# hw-proto01.net
KiCad netlist of a schematic drawn in EAGLE
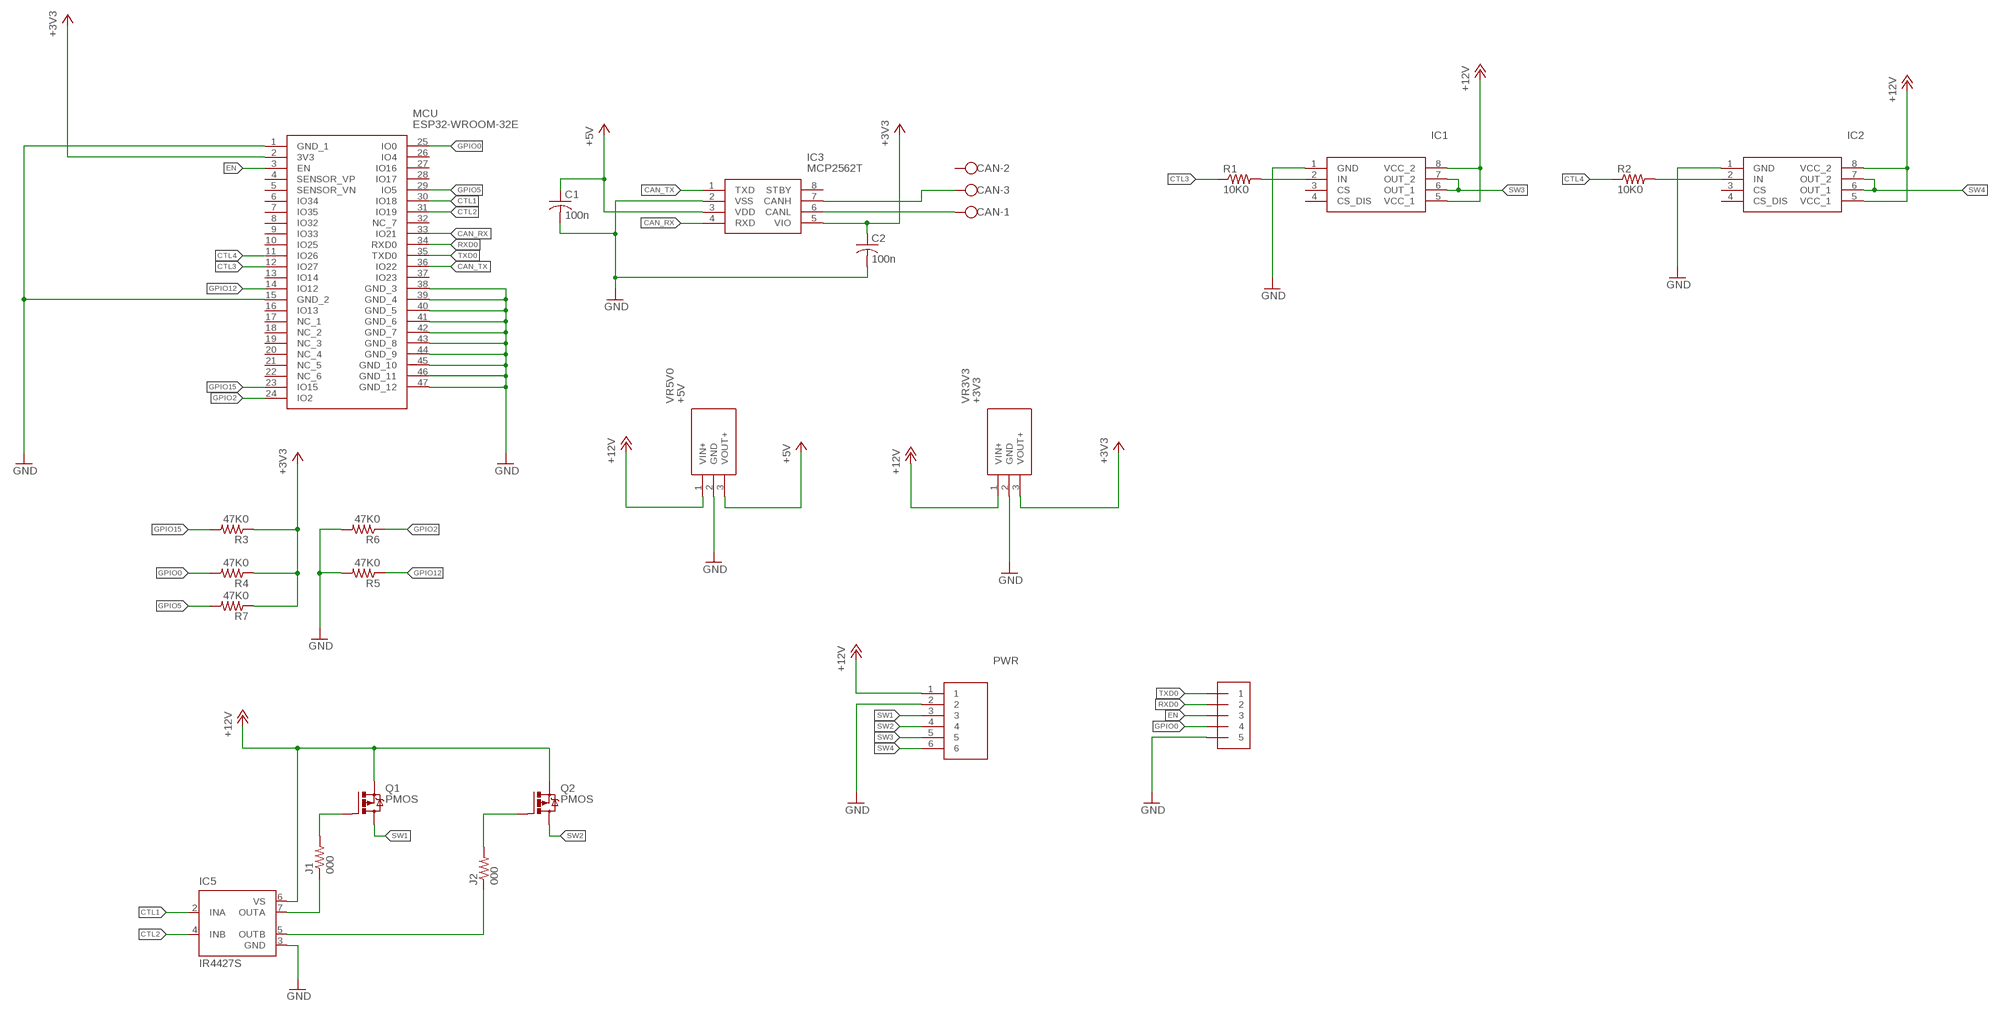
[diagram p0: schematic, sheet 1]

(export (version "E")
  (design (tool "Eeschema 10.0.6"))
  (components
    (comp (ref "C1")
      (value "100n")
      (footprint "eagle-import:C0603K")
      (libsource (lib "eagle-import") (part "C-USC0603K"))
    )
    (comp (ref "C2")
      (value "100n")
      (footprint "eagle-import:C0603K")
      (libsource (lib "eagle-import") (part "C-USC0603K"))
    )
    (comp (ref "CAN")
      (value "W237-103")
      (footprint "eagle-import:W237-103")
      (fields (field (name "MPN") "237-103"))
      (libsource (lib "eagle-import") (part "W237-103"))
    )
    (comp (ref "IC1")
      (value "VN5E160MSTR-E")
      (footprint "eagle-import:SOIC127P600X175-8N")
      (fields (field (name "MOUSER_PART_NUMBER") "511-VN5E160MSTR-E"))
      (libsource (lib "eagle-import") (part "VN5E160MSTR-E"))
    )
    (comp (ref "IC2")
      (value "VN5E160MSTR-E")
      (footprint "eagle-import:SOIC127P600X175-8N")
      (fields (field (name "MOUSER_PART_NUMBER") "511-VN5E160MSTR-E"))
      (libsource (lib "eagle-import") (part "VN5E160MSTR-E"))
    )
    (comp (ref "IC3")
      (value "MCP2562T")
      (footprint "eagle-import:SOIC127P600X175-8N")
      (fields
        (field (name "MANUFACTURER_PART_NUMBER") "MCP2562T-H/SN")
        (field (name "MOUSER_PART_NUMBER") "579-MCP2562T-H/SN")
      )
      (libsource (lib "eagle-import") (part "MCP2562T-H_SN"))
    )
    (comp (ref "IC5")
      (value "IR4427S")
      (footprint "eagle-import:SO08")
      (fields (field (name "MF") "INTERNATIONAL RECTIFIER(IR)") (field (name "MPN") "IR4427STRPBF"))
      (libsource (lib "eagle-import") (part "IR4427S"))
    )
    (comp (ref "J1")
      (value "000")
      (footprint "eagle-import:0207_12")
      (libsource (lib "eagle-import") (part "R-US_0207/12"))
    )
    (comp (ref "J2")
      (value "000")
      (footprint "eagle-import:0207_12")
      (libsource (lib "eagle-import") (part "R-US_0207/12"))
    )
    (comp (ref "MCU")
      (value "ESP32-WROOM-32E")
      (footprint "eagle-import:ESP32WROOM32EN8R2")
      (fields
        (field (name "MANUFACTURER_PART_NUMBER") "ESP32-WROOM-32E-N8R2")
        (field (name "MOUSER_PART_NUMBER") "356-ESP32WRM32EN8R2")
      )
      (libsource (lib "eagle-import") (part "ESP32-WROOM-32E-N8R2"))
    )
    (comp (ref "PROG")
      (value "1X5")
      (footprint "eagle-import:1X05-3.5MM")
      (libsource (lib "eagle-import") (part "1X5"))
    )
    (comp (ref "PWR")
      (value "4DB-P108-06")
      (footprint "eagle-import:4DBP10806")
      (libsource (lib "eagle-import") (part "4DB-P108-06"))
    )
    (comp (ref "Q1")
      (value "PMOS")
      (footprint "eagle-import:D-PAK_TO252AA")
      (libsource (lib "eagle-import") (part "IRF9530DPAK"))
    )
    (comp (ref "Q2")
      (value "PMOS")
      (footprint "eagle-import:D-PAK_TO252AA")
      (libsource (lib "eagle-import") (part "IRF9530DPAK"))
    )
    (comp (ref "R1")
      (value "10K0")
      (footprint "eagle-import:0204_7")
      (libsource (lib "eagle-import") (part "R-US_0204/7"))
    )
    (comp (ref "R2")
      (value "10K0")
      (footprint "eagle-import:0204_7")
      (libsource (lib "eagle-import") (part "R-US_0204/7"))
    )
    (comp (ref "R3")
      (value "47K0")
      (footprint "eagle-import:R0603")
      (libsource (lib "eagle-import") (part "R-US_R0603"))
    )
    (comp (ref "R4")
      (value "47K0")
      (footprint "eagle-import:R0603")
      (libsource (lib "eagle-import") (part "R-US_R0603"))
    )
    (comp (ref "R5")
      (value "47K0")
      (footprint "eagle-import:R0603")
      (libsource (lib "eagle-import") (part "R-US_R0603"))
    )
    (comp (ref "R6")
      (value "47K0")
      (footprint "eagle-import:R0603")
      (libsource (lib "eagle-import") (part "R-US_R0603"))
    )
    (comp (ref "R7")
      (value "47K0")
      (footprint "eagle-import:R0603")
      (libsource (lib "eagle-import") (part "R-US_R0603"))
    )
    (comp (ref "VR3V3")
      (value "+3V3")
      (footprint "eagle-import:TSR-1-2433")
      (fields
        (field (name "MANUFACTURER_PART_NUMBER") "TSR 1-2433E")
        (field (name "MOUSER_PART_NUMBER") "495-TSR1-2433E")
      )
      (libsource (lib "eagle-import") (part "TSR_1-2433E"))
    )
    (comp (ref "VR5V0")
      (value "+5V")
      (footprint "eagle-import:TSR-1-2433")
      (fields
        (field (name "MANUFACTURER_PART_NUMBER") "TSR 1-2433E")
        (field (name "MOUSER_PART_NUMBER") "495-TSR1-2433E")
      )
      (libsource (lib "eagle-import") (part "TSR_1-2433E"))
    )
  )
  (nets
    (net (code "1") (name "+3V3") (class "Default")
      (node (ref "C2") (pin "1") (pinfunction "1_1") (pintype "passive"))
      (node (ref "IC3") (pin "5") (pinfunction "VIO_5") (pintype "bidirectional"))
      (node (ref "MCU") (pin "2") (pinfunction "3V3_2") (pintype "bidirectional"))
      (node (ref "R3") (pin "1") (pinfunction "1_1") (pintype "passive"))
      (node (ref "R4") (pin "1") (pinfunction "1_1") (pintype "passive"))
      (node (ref "R7") (pin "1") (pinfunction "1_1") (pintype "passive"))
      (node (ref "VR3V3") (pin "3") (pinfunction "VOUT+_3") (pintype "output"))
    )
    (net (code "2") (name "+5V") (class "Default")
      (node (ref "C1") (pin "1") (pinfunction "1_1") (pintype "passive"))
      (node (ref "IC3") (pin "3") (pinfunction "VDD_3") (pintype "bidirectional"))
      (node (ref "VR5V0") (pin "3") (pinfunction "VOUT+_3") (pintype "output"))
    )
    (net (code "3") (name "+12V") (class "Default")
      (node (ref "IC1") (pin "5") (pinfunction "VCC_1_5") (pintype "bidirectional"))
      (node (ref "IC1") (pin "8") (pinfunction "VCC_2_8") (pintype "bidirectional"))
      (node (ref "IC2") (pin "5") (pinfunction "VCC_1_5") (pintype "bidirectional"))
      (node (ref "IC2") (pin "8") (pinfunction "VCC_2_8") (pintype "bidirectional"))
      (node (ref "IC5") (pin "6") (pinfunction "VS_6") (pintype "power_in"))
      (node (ref "PWR") (pin "1") (pinfunction "1_1") (pintype "bidirectional"))
      (node (ref "Q1") (pin "4") (pinfunction "S_4") (pintype "passive"))
      (node (ref "Q2") (pin "4") (pinfunction "S_4") (pintype "passive"))
      (node (ref "VR3V3") (pin "1") (pinfunction "VIN+_1") (pintype "input"))
      (node (ref "VR5V0") (pin "1") (pinfunction "VIN+_1") (pintype "input"))
    )
    (net (code "4") (name "CAN_RX") (class "Default")
      (node (ref "IC3") (pin "4") (pinfunction "RXD_4") (pintype "bidirectional"))
      (node (ref "MCU") (pin "33") (pinfunction "IO21_33") (pintype "bidirectional"))
    )
    (net (code "5") (name "CAN_TX") (class "Default")
      (node (ref "IC3") (pin "1") (pinfunction "TXD_1") (pintype "bidirectional"))
      (node (ref "MCU") (pin "36") (pinfunction "IO22_36") (pintype "bidirectional"))
    )
    (net (code "6") (name "CTL1") (class "Default")
      (node (ref "IC5") (pin "2") (pinfunction "INA_2") (pintype "input"))
      (node (ref "MCU") (pin "30") (pinfunction "IO18_30") (pintype "bidirectional"))
    )
    (net (code "7") (name "CTL2") (class "Default")
      (node (ref "IC5") (pin "4") (pinfunction "INB_4") (pintype "input"))
      (node (ref "MCU") (pin "31") (pinfunction "IO19_31") (pintype "bidirectional"))
    )
    (net (code "8") (name "CTL3") (class "Default")
      (node (ref "MCU") (pin "12") (pinfunction "IO27_12") (pintype "bidirectional"))
      (node (ref "R1") (pin "1") (pinfunction "1_1") (pintype "passive"))
    )
    (net (code "9") (name "CTL4") (class "Default")
      (node (ref "MCU") (pin "11") (pinfunction "IO26_11") (pintype "bidirectional"))
      (node (ref "R2") (pin "1") (pinfunction "1_1") (pintype "passive"))
    )
    (net (code "10") (name "EN") (class "Default")
      (node (ref "MCU") (pin "3") (pinfunction "EN_3") (pintype "bidirectional"))
      (node (ref "PROG") (pin "3") (pinfunction "3_3") (pintype "passive"))
    )
    (net (code "11") (name "GND") (class "Default")
      (node (ref "C1") (pin "2") (pinfunction "2_2") (pintype "passive"))
      (node (ref "C2") (pin "2") (pinfunction "2_2") (pintype "passive"))
      (node (ref "IC1") (pin "1") (pinfunction "GND_1") (pintype "bidirectional"))
      (node (ref "IC2") (pin "1") (pinfunction "GND_1") (pintype "bidirectional"))
      (node (ref "IC3") (pin "2") (pinfunction "VSS_2") (pintype "bidirectional"))
      (node (ref "IC5") (pin "3") (pinfunction "GND_3") (pintype "power_in"))
      (node (ref "MCU") (pin "1") (pinfunction "GND_1_1") (pintype "bidirectional"))
      (node (ref "MCU") (pin "15") (pinfunction "GND_2_15") (pintype "bidirectional"))
      (node (ref "MCU") (pin "38") (pinfunction "GND_3_38") (pintype "bidirectional"))
      (node (ref "MCU") (pin "39") (pinfunction "GND_4_39") (pintype "bidirectional"))
      (node (ref "MCU") (pin "40") (pinfunction "GND_5_40") (pintype "bidirectional"))
      (node (ref "MCU") (pin "41") (pinfunction "GND_6_41") (pintype "bidirectional"))
      (node (ref "MCU") (pin "42") (pinfunction "GND_7_42") (pintype "bidirectional"))
      (node (ref "MCU") (pin "43") (pinfunction "GND_8_43") (pintype "bidirectional"))
      (node (ref "MCU") (pin "44") (pinfunction "GND_9_44") (pintype "bidirectional"))
      (node (ref "MCU") (pin "45") (pinfunction "GND_10_45") (pintype "bidirectional"))
      (node (ref "MCU") (pin "46") (pinfunction "GND_11_46") (pintype "bidirectional"))
      (node (ref "MCU") (pin "47") (pinfunction "GND_12_47") (pintype "bidirectional"))
      (node (ref "PROG") (pin "5") (pinfunction "5_5") (pintype "passive"))
      (node (ref "PWR") (pin "2") (pinfunction "2_2") (pintype "bidirectional"))
      (node (ref "R5") (pin "2") (pinfunction "2_2") (pintype "passive"))
      (node (ref "R6") (pin "2") (pinfunction "2_2") (pintype "passive"))
      (node (ref "VR3V3") (pin "2") (pinfunction "GND_2") (pintype "power_in"))
      (node (ref "VR5V0") (pin "2") (pinfunction "GND_2") (pintype "power_in"))
    )
    (net (code "12") (name "GPIO0") (class "Default")
      (node (ref "MCU") (pin "25") (pinfunction "IO0_25") (pintype "bidirectional"))
      (node (ref "PROG") (pin "4") (pinfunction "4_4") (pintype "passive"))
      (node (ref "R4") (pin "2") (pinfunction "2_2") (pintype "passive"))
    )
    (net (code "13") (name "GPIO2") (class "Default")
      (node (ref "MCU") (pin "24") (pinfunction "IO2_24") (pintype "bidirectional"))
      (node (ref "R6") (pin "1") (pinfunction "1_1") (pintype "passive"))
    )
    (net (code "14") (name "GPIO5") (class "Default")
      (node (ref "MCU") (pin "29") (pinfunction "IO5_29") (pintype "bidirectional"))
      (node (ref "R7") (pin "2") (pinfunction "2_2") (pintype "passive"))
    )
    (net (code "15") (name "GPIO12") (class "Default")
      (node (ref "MCU") (pin "14") (pinfunction "IO12_14") (pintype "bidirectional"))
      (node (ref "R5") (pin "1") (pinfunction "1_1") (pintype "passive"))
    )
    (net (code "16") (name "GPIO15") (class "Default")
      (node (ref "MCU") (pin "23") (pinfunction "IO15_23") (pintype "bidirectional"))
      (node (ref "R3") (pin "2") (pinfunction "2_2") (pintype "passive"))
    )
    (net (code "17") (name "Net-(CANA-KL)") (class "Default")
      (node (ref "CAN") (pin "1") (pinfunction "KL_1") (pintype "passive"))
      (node (ref "IC3") (pin "6") (pinfunction "CANL_6") (pintype "bidirectional"))
    )
    (net (code "18") (name "Net-(CANC-KL)") (class "Default")
      (node (ref "CAN") (pin "3") (pinfunction "KL_3") (pintype "passive"))
      (node (ref "IC3") (pin "7") (pinfunction "CANH_7") (pintype "bidirectional"))
    )
    (net (code "19") (name "Net-(IC1-IN)") (class "Default")
      (node (ref "IC1") (pin "2") (pinfunction "IN_2") (pintype "bidirectional"))
      (node (ref "R1") (pin "2") (pinfunction "2_2") (pintype "passive"))
    )
    (net (code "20") (name "Net-(IC2-IN)") (class "Default")
      (node (ref "IC2") (pin "2") (pinfunction "IN_2") (pintype "bidirectional"))
      (node (ref "R2") (pin "2") (pinfunction "2_2") (pintype "passive"))
    )
    (net (code "21") (name "Net-(IC5-OUTA)") (class "Default")
      (node (ref "IC5") (pin "7") (pinfunction "OUTA_7") (pintype "output"))
      (node (ref "J1") (pin "1") (pinfunction "1_1") (pintype "passive"))
    )
    (net (code "22") (name "Net-(IC5-OUTB)") (class "Default")
      (node (ref "IC5") (pin "5") (pinfunction "OUTB_5") (pintype "output"))
      (node (ref "J2") (pin "1") (pinfunction "1_1") (pintype "passive"))
    )
    (net (code "23") (name "Net-(Q1-G)") (class "Default")
      (node (ref "J1") (pin "2") (pinfunction "2_2") (pintype "passive"))
      (node (ref "Q1") (pin "1") (pinfunction "G_1") (pintype "passive"))
    )
    (net (code "24") (name "Net-(Q2-G)") (class "Default")
      (node (ref "J2") (pin "2") (pinfunction "2_2") (pintype "passive"))
      (node (ref "Q2") (pin "1") (pinfunction "G_1") (pintype "passive"))
    )
    (net (code "25") (name "RXD0") (class "Default")
      (node (ref "MCU") (pin "34") (pinfunction "RXD0_34") (pintype "bidirectional"))
      (node (ref "PROG") (pin "2") (pinfunction "2_2") (pintype "passive"))
    )
    (net (code "26") (name "SW1") (class "Default")
      (node (ref "PWR") (pin "3") (pinfunction "3_3") (pintype "bidirectional"))
      (node (ref "Q1") (pin "3") (pinfunction "D_3") (pintype "passive"))
    )
    (net (code "27") (name "SW2") (class "Default")
      (node (ref "PWR") (pin "4") (pinfunction "4_4") (pintype "bidirectional"))
      (node (ref "Q2") (pin "3") (pinfunction "D_3") (pintype "passive"))
    )
    (net (code "28") (name "SW3") (class "Default")
      (node (ref "IC1") (pin "6") (pinfunction "OUT_1_6") (pintype "bidirectional"))
      (node (ref "IC1") (pin "7") (pinfunction "OUT_2_7") (pintype "bidirectional"))
      (node (ref "PWR") (pin "5") (pinfunction "5_5") (pintype "bidirectional"))
    )
    (net (code "29") (name "SW4") (class "Default")
      (node (ref "IC2") (pin "6") (pinfunction "OUT_1_6") (pintype "bidirectional"))
      (node (ref "IC2") (pin "7") (pinfunction "OUT_2_7") (pintype "bidirectional"))
      (node (ref "PWR") (pin "6") (pinfunction "6_6") (pintype "bidirectional"))
    )
    (net (code "30") (name "TXD0") (class "Default")
      (node (ref "MCU") (pin "35") (pinfunction "TXD0_35") (pintype "bidirectional"))
      (node (ref "PROG") (pin "1") (pinfunction "1_1") (pintype "passive"))
    )
    (net (code "31") (name "unconnected-(CANB-KL-Pad2)") (class "Default")
      (node (ref "CAN") (pin "2") (pinfunction "KL_2") (pintype "passive"))
    )
    (net (code "32") (name "unconnected-(IC1-CS-Pad3)") (class "Default")
      (node (ref "IC1") (pin "3") (pinfunction "CS_3") (pintype "bidirectional"))
    )
    (net (code "33") (name "unconnected-(IC1-CS_DIS-Pad4)") (class "Default")
      (node (ref "IC1") (pin "4") (pinfunction "CS_DIS_4") (pintype "bidirectional"))
    )
    (net (code "34") (name "unconnected-(IC2-CS-Pad3)") (class "Default")
      (node (ref "IC2") (pin "3") (pinfunction "CS_3") (pintype "bidirectional"))
    )
    (net (code "35") (name "unconnected-(IC2-CS_DIS-Pad4)") (class "Default")
      (node (ref "IC2") (pin "4") (pinfunction "CS_DIS_4") (pintype "bidirectional"))
    )
    (net (code "36") (name "unconnected-(IC3-STBY-Pad8)") (class "Default")
      (node (ref "IC3") (pin "8") (pinfunction "STBY_8") (pintype "bidirectional"))
    )
    (net (code "37") (name "unconnected-(MCU-IO4-Pad26)") (class "Default")
      (node (ref "MCU") (pin "26") (pinfunction "IO4_26") (pintype "bidirectional"))
    )
    (net (code "38") (name "unconnected-(MCU-IO13-Pad16)") (class "Default")
      (node (ref "MCU") (pin "16") (pinfunction "IO13_16") (pintype "bidirectional"))
    )
    (net (code "39") (name "unconnected-(MCU-IO14-Pad13)") (class "Default")
      (node (ref "MCU") (pin "13") (pinfunction "IO14_13") (pintype "bidirectional"))
    )
    (net (code "40") (name "unconnected-(MCU-IO16-Pad27)") (class "Default")
      (node (ref "MCU") (pin "27") (pinfunction "IO16_27") (pintype "bidirectional"))
    )
    (net (code "41") (name "unconnected-(MCU-IO17-Pad28)") (class "Default")
      (node (ref "MCU") (pin "28") (pinfunction "IO17_28") (pintype "bidirectional"))
    )
    (net (code "42") (name "unconnected-(MCU-IO23-Pad37)") (class "Default")
      (node (ref "MCU") (pin "37") (pinfunction "IO23_37") (pintype "bidirectional"))
    )
    (net (code "43") (name "unconnected-(MCU-IO25-Pad10)") (class "Default")
      (node (ref "MCU") (pin "10") (pinfunction "IO25_10") (pintype "bidirectional"))
    )
    (net (code "44") (name "unconnected-(MCU-IO32-Pad8)") (class "Default")
      (node (ref "MCU") (pin "8") (pinfunction "IO32_8") (pintype "bidirectional"))
    )
    (net (code "45") (name "unconnected-(MCU-IO33-Pad9)") (class "Default")
      (node (ref "MCU") (pin "9") (pinfunction "IO33_9") (pintype "bidirectional"))
    )
    (net (code "46") (name "unconnected-(MCU-IO34-Pad6)") (class "Default")
      (node (ref "MCU") (pin "6") (pinfunction "IO34_6") (pintype "bidirectional"))
    )
    (net (code "47") (name "unconnected-(MCU-IO35-Pad7)") (class "Default")
      (node (ref "MCU") (pin "7") (pinfunction "IO35_7") (pintype "bidirectional"))
    )
    (net (code "48") (name "unconnected-(MCU-NC_1-Pad17)") (class "Default")
      (node (ref "MCU") (pin "17") (pinfunction "NC_1_17") (pintype "bidirectional"))
    )
    (net (code "49") (name "unconnected-(MCU-NC_2-Pad18)") (class "Default")
      (node (ref "MCU") (pin "18") (pinfunction "NC_2_18") (pintype "bidirectional"))
    )
    (net (code "50") (name "unconnected-(MCU-NC_3-Pad19)") (class "Default")
      (node (ref "MCU") (pin "19") (pinfunction "NC_3_19") (pintype "bidirectional"))
    )
    (net (code "51") (name "unconnected-(MCU-NC_4-Pad20)") (class "Default")
      (node (ref "MCU") (pin "20") (pinfunction "NC_4_20") (pintype "bidirectional"))
    )
    (net (code "52") (name "unconnected-(MCU-NC_5-Pad21)") (class "Default")
      (node (ref "MCU") (pin "21") (pinfunction "NC_5_21") (pintype "bidirectional"))
    )
    (net (code "53") (name "unconnected-(MCU-NC_6-Pad22)") (class "Default")
      (node (ref "MCU") (pin "22") (pinfunction "NC_6_22") (pintype "bidirectional"))
    )
    (net (code "54") (name "unconnected-(MCU-NC_7-Pad32)") (class "Default")
      (node (ref "MCU") (pin "32") (pinfunction "NC_7_32") (pintype "bidirectional"))
    )
    (net (code "55") (name "unconnected-(MCU-SENSOR_VN-Pad5)") (class "Default")
      (node (ref "MCU") (pin "5") (pinfunction "SENSOR_VN_5") (pintype "bidirectional"))
    )
    (net (code "56") (name "unconnected-(MCU-SENSOR_VP-Pad4)") (class "Default")
      (node (ref "MCU") (pin "4") (pinfunction "SENSOR_VP_4") (pintype "bidirectional"))
    )
  )
)
